# led-motion-sensor-v1.net
KiCad netlist of a schematic drawn in EAGLE
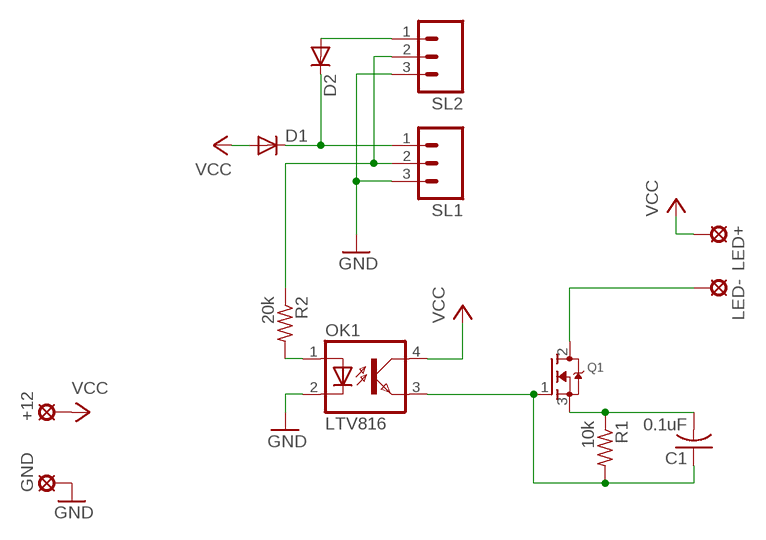
[diagram p0: schematic, sheet 1]

(export (version "E")
  (design (tool "Eeschema 10.0.6"))
  (components
    (comp (ref "+12")
      (value "LSP10")
      (footprint "eagle-import:LSP10")
      (libsource (lib "eagle-import") (part "LSP10"))
    )
    (comp (ref "C1")
      (value "0.1uF")
      (footprint "eagle-import:C0603K")
      (libsource (lib "eagle-import") (part "C-USC0603K"))
    )
    (comp (ref "D1")
      (value "DIODE-MICROMELF-W")
      (footprint "eagle-import:MICROMELF-W")
      (libsource (lib "eagle-import") (part "DIODE-MICROMELF-W"))
    )
    (comp (ref "D2")
      (value "DIODE-MICROMELF-W")
      (footprint "eagle-import:MICROMELF-W")
      (libsource (lib "eagle-import") (part "DIODE-MICROMELF-W"))
    )
    (comp (ref "GND")
      (value "LSP10")
      (footprint "eagle-import:LSP10")
      (libsource (lib "eagle-import") (part "LSP10"))
    )
    (comp (ref "LED+")
      (value "LSP10")
      (footprint "eagle-import:LSP10")
      (libsource (lib "eagle-import") (part "LSP10"))
    )
    (comp (ref "LED-")
      (value "LSP10")
      (footprint "eagle-import:LSP10")
      (libsource (lib "eagle-import") (part "LSP10"))
    )
    (comp (ref "OK1")
      (value "LTV816")
      (footprint "eagle-import:DIL04")
      (libsource (lib "eagle-import") (part "LTV816"))
    )
    (comp (ref "Q1")
      (value "MOSFET-NGDS_TO220V")
      (footprint "eagle-import:TO220V")
      (libsource (lib "eagle-import") (part "MOSFET-NGDS_TO220V"))
    )
    (comp (ref "R1")
      (value "10k")
      (footprint "eagle-import:R0603")
      (libsource (lib "eagle-import") (part "R-US_R0603"))
    )
    (comp (ref "R2")
      (value "20k")
      (footprint "eagle-import:R0603")
      (libsource (lib "eagle-import") (part "R-US_R0603"))
    )
    (comp (ref "SL1")
      (value "M03")
      (footprint "eagle-import:03P")
      (libsource (lib "eagle-import") (part "M03"))
    )
    (comp (ref "SL2")
      (value "M03")
      (footprint "eagle-import:03P")
      (libsource (lib "eagle-import") (part "M03"))
    )
  )
  (nets
    (net (code "1") (name "GND") (class "Default")
      (node (ref "GND") (pin "MP") (pinfunction "MP_MP") (pintype "passive"))
      (node (ref "OK1") (pin "2") (pinfunction "C_2") (pintype "passive"))
      (node (ref "SL1") (pin "3") (pinfunction "3_3") (pintype "passive"))
      (node (ref "SL2") (pin "3") (pinfunction "3_3") (pintype "passive"))
    )
    (net (code "2") (name "Net-(D1-PadC)") (class "Default")
      (node (ref "D1") (pin "C") (pinfunction "C_C") (pintype "passive"))
      (node (ref "D2") (pin "C") (pinfunction "C_C") (pintype "passive"))
      (node (ref "SL1") (pin "1") (pinfunction "1_1") (pintype "passive"))
    )
    (net (code "3") (name "Net-(D2-PadA)") (class "Default")
      (node (ref "D2") (pin "A") (pinfunction "A_A") (pintype "passive"))
      (node (ref "SL2") (pin "1") (pinfunction "1_1") (pintype "passive"))
    )
    (net (code "4") (name "Net-(OK1-A)") (class "Default")
      (node (ref "OK1") (pin "1") (pinfunction "A_1") (pintype "passive"))
      (node (ref "R2") (pin "2") (pinfunction "2_2") (pintype "passive"))
    )
    (net (code "5") (name "Net-(OK1-EMIT)") (class "Default")
      (node (ref "C1") (pin "1") (pinfunction "1_1") (pintype "passive"))
      (node (ref "OK1") (pin "3") (pinfunction "EMIT_3") (pintype "passive"))
      (node (ref "Q1") (pin "1") (pinfunction "G_1") (pintype "bidirectional"))
      (node (ref "R1") (pin "2") (pinfunction "2_2") (pintype "passive"))
    )
    (net (code "6") (name "Net-(Q1-D)") (class "Default")
      (node (ref "LED-") (pin "MP") (pinfunction "MP_MP") (pintype "passive"))
      (node (ref "Q1") (pin "2") (pinfunction "D_2") (pintype "bidirectional"))
    )
    (net (code "7") (name "Net-(Q1-S)") (class "Default")
      (node (ref "C1") (pin "2") (pinfunction "2_2") (pintype "passive"))
      (node (ref "Q1") (pin "3") (pinfunction "S_3") (pintype "bidirectional"))
      (node (ref "R1") (pin "1") (pinfunction "1_1") (pintype "passive"))
    )
    (net (code "8") (name "Net-(R2-Pad1)") (class "Default")
      (node (ref "R2") (pin "1") (pinfunction "1_1") (pintype "passive"))
      (node (ref "SL1") (pin "2") (pinfunction "2_2") (pintype "passive"))
      (node (ref "SL2") (pin "2") (pinfunction "2_2") (pintype "passive"))
    )
    (net (code "9") (name "VCC") (class "Default")
      (node (ref "+12") (pin "MP") (pinfunction "MP_MP") (pintype "passive"))
      (node (ref "D1") (pin "A") (pinfunction "A_A") (pintype "passive"))
      (node (ref "LED+") (pin "MP") (pinfunction "MP_MP") (pintype "passive"))
      (node (ref "OK1") (pin "4") (pinfunction "COL_4") (pintype "passive"))
    )
  )
)
